# AND_GATE.net
KiCad netlist of a schematic drawn in EAGLE
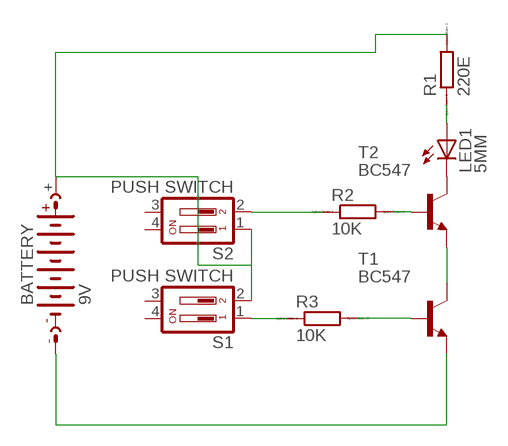
[diagram p0: schematic, sheet 1]

(export (version "E")
  (design (tool "Eeschema 10.0.6"))
  (components
    (comp (ref "BATTERY")
      (value "9V")
      (footprint "eagle-import:AB9V")
      (libsource (lib "eagle-import") (part "AB9V"))
    )
    (comp (ref "LED1")
      (value "5MM")
      (footprint "eagle-import:LED5MM")
      (libsource (lib "eagle-import") (part "LED5MM"))
    )
    (comp (ref "R1")
      (value "220E")
      (footprint "eagle-import:0204_7")
      (libsource (lib "eagle-import") (part "R0204/7"))
    )
    (comp (ref "R2")
      (value "10K")
      (footprint "eagle-import:0204_7")
      (libsource (lib "eagle-import") (part "R0204/7"))
    )
    (comp (ref "R3")
      (value "10K")
      (footprint "eagle-import:0204_7")
      (libsource (lib "eagle-import") (part "R0204/7"))
    )
    (comp (ref "S1")
      (value "PUSH SWITCH")
      (footprint "eagle-import:DS-02")
      (libsource (lib "eagle-import") (part "DS02"))
    )
    (comp (ref "S2")
      (value "PUSH SWITCH")
      (footprint "eagle-import:DS-02")
      (libsource (lib "eagle-import") (part "DS02"))
    )
    (comp (ref "T1")
      (value "BC547")
      (footprint "eagle-import:TO92")
      (libsource (lib "eagle-import") (part "BC547"))
    )
    (comp (ref "T2")
      (value "BC547")
      (footprint "eagle-import:TO92")
      (libsource (lib "eagle-import") (part "BC547"))
    )
  )
  (nets
    (net (code "1") (name "Net-(BATTERY-Pad+)") (class "Default")
      (node (ref "BATTERY") (pin "+") (pinfunction "+_+") (pintype "passive"))
      (node (ref "R1") (pin "2") (pinfunction "2_2") (pintype "passive"))
      (node (ref "S1") (pin "2") (pinfunction "2_2") (pintype "passive"))
      (node (ref "S2") (pin "1") (pinfunction "1_1") (pintype "passive"))
    )
    (net (code "2") (name "Net-(LED1-C)") (class "Default")
      (node (ref "LED1") (pin "K") (pinfunction "C_K") (pintype "passive"))
      (node (ref "T2") (pin "3") (pinfunction "C_3") (pintype "passive"))
    )
    (net (code "3") (name "Net-(LED1-PadA)") (class "Default")
      (node (ref "LED1") (pin "A") (pinfunction "A_A") (pintype "passive"))
      (node (ref "R1") (pin "1") (pinfunction "1_1") (pintype "passive"))
    )
    (net (code "4") (name "Net-(R2-Pad1)") (class "Default")
      (node (ref "R2") (pin "1") (pinfunction "1_1") (pintype "passive"))
      (node (ref "S2") (pin "2") (pinfunction "2_2") (pintype "passive"))
    )
    (net (code "5") (name "Net-(R3-Pad1)") (class "Default")
      (node (ref "R3") (pin "1") (pinfunction "1_1") (pintype "passive"))
      (node (ref "S1") (pin "1") (pinfunction "1_1") (pintype "passive"))
    )
    (net (code "6") (name "Net-(T1-B)") (class "Default")
      (node (ref "R3") (pin "2") (pinfunction "2_2") (pintype "passive"))
      (node (ref "T1") (pin "2") (pinfunction "B_2") (pintype "passive"))
    )
    (net (code "7") (name "Net-(T1-C)") (class "Default")
      (node (ref "T1") (pin "3") (pinfunction "C_3") (pintype "passive"))
      (node (ref "T2") (pin "1") (pinfunction "E_1") (pintype "passive"))
    )
    (net (code "8") (name "Net-(T1-E)") (class "Default")
      (node (ref "BATTERY") (pin "-") (pinfunction "-_-") (pintype "passive"))
      (node (ref "T1") (pin "1") (pinfunction "E_1") (pintype "passive"))
    )
    (net (code "9") (name "Net-(T2-B)") (class "Default")
      (node (ref "R2") (pin "2") (pinfunction "2_2") (pintype "passive"))
      (node (ref "T2") (pin "2") (pinfunction "B_2") (pintype "passive"))
    )
    (net (code "10") (name "unconnected-(S1-Pad3)") (class "Default")
      (node (ref "S1") (pin "3") (pinfunction "3_3") (pintype "passive"))
    )
    (net (code "11") (name "unconnected-(S1-Pad4)") (class "Default")
      (node (ref "S1") (pin "4") (pinfunction "4_4") (pintype "passive"))
    )
    (net (code "12") (name "unconnected-(S2-Pad3)") (class "Default")
      (node (ref "S2") (pin "3") (pinfunction "3_3") (pintype "passive"))
    )
    (net (code "13") (name "unconnected-(S2-Pad4)") (class "Default")
      (node (ref "S2") (pin "4") (pinfunction "4_4") (pintype "passive"))
    )
  )
)
